# Fan-and-temperature-controller.net
KiCad netlist of a schematic drawn in EAGLE
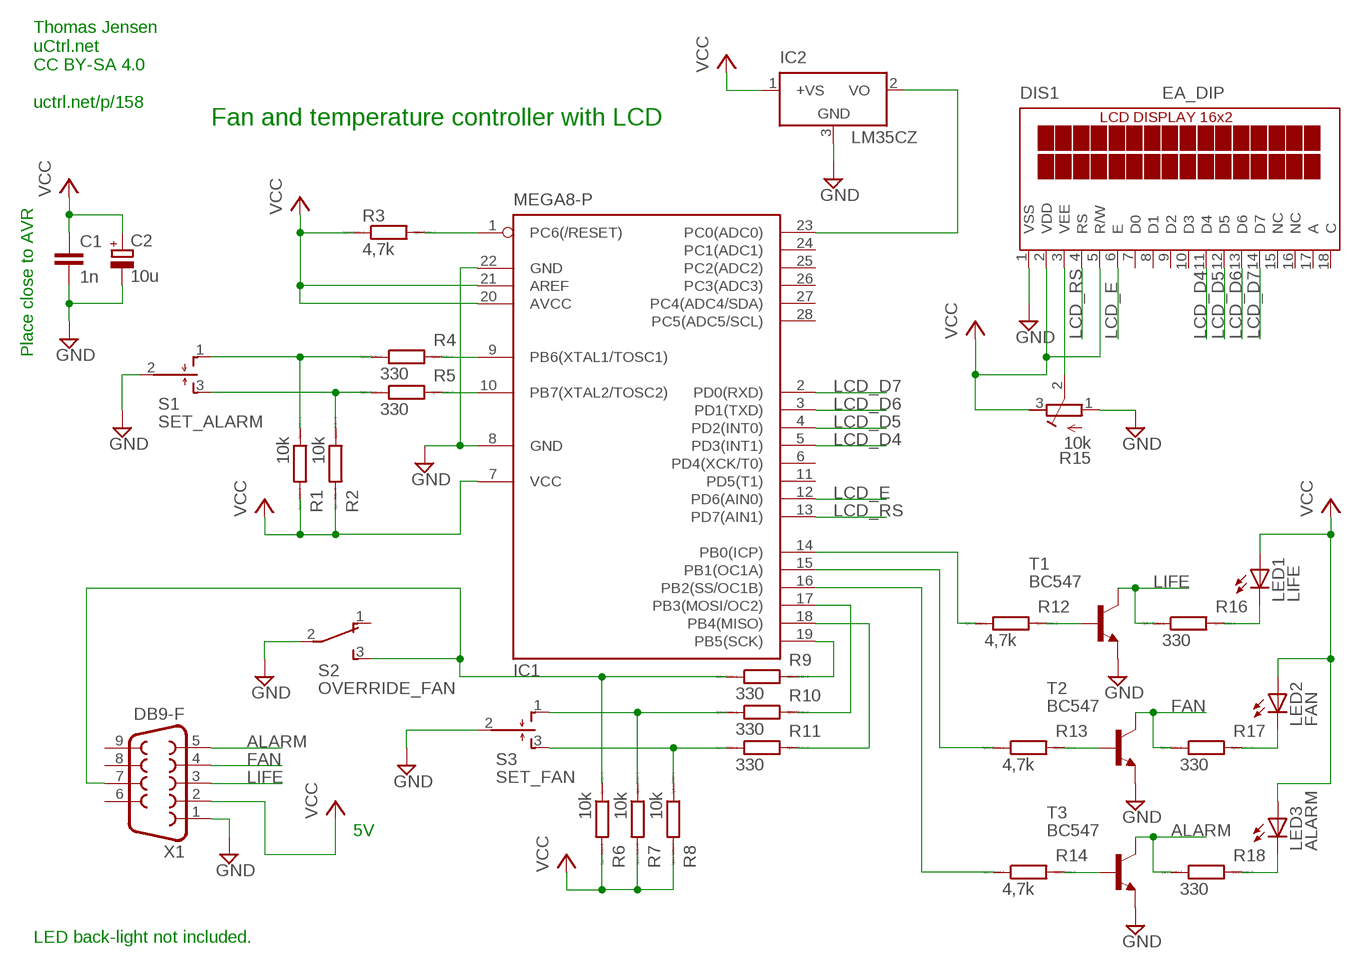
[diagram p0: schematic, sheet 1]

(export (version "E")
  (design (tool "Eeschema 10.0.6"))
  (components
    (comp (ref "C1")
      (value "1n")
      (footprint "eagle-import:C025-024X044")
      (libsource (lib "eagle-import") (part "C-EU025-024X044"))
    )
    (comp (ref "C2")
      (value "10u")
      (footprint "eagle-import:E1,8-4")
      (libsource (lib "eagle-import") (part "CPOL-EUE1.8-4"))
    )
    (comp (ref "DIS1")
      (value "EA_DIP")
      (footprint "eagle-import:EA_DIP")
      (libsource (lib "eagle-import") (part "EA_DIP"))
    )
    (comp (ref "IC1")
      (value "MEGA8-P")
      (footprint "eagle-import:DIL28-3")
      (libsource (lib "eagle-import") (part "MEGA8-P"))
    )
    (comp (ref "IC2")
      (value "LM35CZ")
      (footprint "eagle-import:TO92")
      (libsource (lib "eagle-import") (part "LM35CZ"))
    )
    (comp (ref "LED1")
      (value "LIFE")
      (footprint "eagle-import:LED5MM")
      (libsource (lib "eagle-import") (part "LED5MM"))
    )
    (comp (ref "LED2")
      (value "FAN")
      (footprint "eagle-import:LED5MM")
      (libsource (lib "eagle-import") (part "LED5MM"))
    )
    (comp (ref "LED3")
      (value "ALARM")
      (footprint "eagle-import:LED5MM")
      (libsource (lib "eagle-import") (part "LED5MM"))
    )
    (comp (ref "R1")
      (value "10k")
      (footprint "eagle-import:0204_7")
      (libsource (lib "eagle-import") (part "R0204/7"))
    )
    (comp (ref "R2")
      (value "10k")
      (footprint "eagle-import:0204_7")
      (libsource (lib "eagle-import") (part "R0204/7"))
    )
    (comp (ref "R3")
      (value "4,7k")
      (footprint "eagle-import:0204_7")
      (libsource (lib "eagle-import") (part "R0204/7"))
    )
    (comp (ref "R4")
      (value "330")
      (footprint "eagle-import:0204_7")
      (libsource (lib "eagle-import") (part "R0204/7"))
    )
    (comp (ref "R5")
      (value "330")
      (footprint "eagle-import:0204_7")
      (libsource (lib "eagle-import") (part "R0204/7"))
    )
    (comp (ref "R6")
      (value "10k")
      (footprint "eagle-import:0204_7")
      (libsource (lib "eagle-import") (part "R0204/7"))
    )
    (comp (ref "R7")
      (value "10k")
      (footprint "eagle-import:0204_7")
      (libsource (lib "eagle-import") (part "R0204/7"))
    )
    (comp (ref "R8")
      (value "10k")
      (footprint "eagle-import:0204_7")
      (libsource (lib "eagle-import") (part "R0204/7"))
    )
    (comp (ref "R9")
      (value "330")
      (footprint "eagle-import:0204_7")
      (libsource (lib "eagle-import") (part "R0204/7"))
    )
    (comp (ref "R10")
      (value "330")
      (footprint "eagle-import:0204_7")
      (libsource (lib "eagle-import") (part "R0204/7"))
    )
    (comp (ref "R11")
      (value "330")
      (footprint "eagle-import:0204_7")
      (libsource (lib "eagle-import") (part "R0204/7"))
    )
    (comp (ref "R12")
      (value "4,7k")
      (footprint "eagle-import:0204_7")
      (libsource (lib "eagle-import") (part "R0204/7"))
    )
    (comp (ref "R13")
      (value "4,7k")
      (footprint "eagle-import:0204_7")
      (libsource (lib "eagle-import") (part "R0204/7"))
    )
    (comp (ref "R14")
      (value "4,7k")
      (footprint "eagle-import:0204_7")
      (libsource (lib "eagle-import") (part "R0204/7"))
    )
    (comp (ref "R15")
      (value "10k")
      (footprint "eagle-import:RTRIM3339P")
      (libsource (lib "eagle-import") (part "R-TRIMM3339P"))
    )
    (comp (ref "R16")
      (value "330")
      (footprint "eagle-import:0204_7")
      (libsource (lib "eagle-import") (part "R0204/7"))
    )
    (comp (ref "R17")
      (value "330")
      (footprint "eagle-import:0204_7")
      (libsource (lib "eagle-import") (part "R0204/7"))
    )
    (comp (ref "R18")
      (value "330")
      (footprint "eagle-import:0204_7")
      (libsource (lib "eagle-import") (part "R0204/7"))
    )
    (comp (ref "S1")
      (value "SET_ALARM")
      (footprint "eagle-import:TL3XPO")
      (libsource (lib "eagle-import") (part "TL37PO"))
    )
    (comp (ref "S2")
      (value "OVERRIDE_FAN")
      (footprint "eagle-import:TL3XPO")
      (libsource (lib "eagle-import") (part "TL36PO"))
    )
    (comp (ref "S3")
      (value "SET_FAN")
      (footprint "eagle-import:TL3XPO")
      (libsource (lib "eagle-import") (part "TL37PO"))
    )
    (comp (ref "T1")
      (value "BC547")
      (footprint "eagle-import:TO92")
      (libsource (lib "eagle-import") (part "BC547"))
    )
    (comp (ref "T2")
      (value "BC547")
      (footprint "eagle-import:TO92")
      (libsource (lib "eagle-import") (part "BC547"))
    )
    (comp (ref "T3")
      (value "BC547")
      (footprint "eagle-import:TO92")
      (libsource (lib "eagle-import") (part "BC547"))
    )
    (comp (ref "X1")
      (value "DB9-F")
      (footprint "eagle-import:F09D")
      (libsource (lib "eagle-import") (part "F09D"))
    )
  )
  (nets
    (net (code "1") (name "/ALARM") (class "Default")
      (node (ref "R18") (pin "1") (pinfunction "1_1") (pintype "passive"))
      (node (ref "T3") (pin "3") (pinfunction "C_3") (pintype "passive"))
      (node (ref "X1") (pin "5") (pinfunction "5_5") (pintype "passive"))
    )
    (net (code "2") (name "/FAN") (class "Default")
      (node (ref "R17") (pin "1") (pinfunction "1_1") (pintype "passive"))
      (node (ref "T2") (pin "3") (pinfunction "C_3") (pintype "passive"))
      (node (ref "X1") (pin "4") (pinfunction "4_4") (pintype "passive"))
    )
    (net (code "3") (name "/LCD_D4") (class "Default")
      (node (ref "DIS1") (pin "11") (pinfunction "D4_11") (pintype "input"))
      (node (ref "IC1") (pin "5") (pinfunction "PD3(INT1)_5") (pintype "bidirectional"))
    )
    (net (code "4") (name "/LCD_D5") (class "Default")
      (node (ref "DIS1") (pin "12") (pinfunction "D5_12") (pintype "input"))
      (node (ref "IC1") (pin "4") (pinfunction "PD2(INT0)_4") (pintype "bidirectional"))
    )
    (net (code "5") (name "/LCD_D6") (class "Default")
      (node (ref "DIS1") (pin "13") (pinfunction "D6_13") (pintype "input"))
      (node (ref "IC1") (pin "3") (pinfunction "PD1(TXD)_3") (pintype "bidirectional"))
    )
    (net (code "6") (name "/LCD_D7") (class "Default")
      (node (ref "DIS1") (pin "14") (pinfunction "D7_14") (pintype "input"))
      (node (ref "IC1") (pin "2") (pinfunction "PD0(RXD)_2") (pintype "bidirectional"))
    )
    (net (code "7") (name "/LCD_E") (class "Default")
      (node (ref "DIS1") (pin "6") (pinfunction "E_6") (pintype "input"))
      (node (ref "IC1") (pin "12") (pinfunction "PD6(AIN0)_12") (pintype "bidirectional"))
    )
    (net (code "8") (name "/LCD_RS") (class "Default")
      (node (ref "DIS1") (pin "4") (pinfunction "RS_4") (pintype "input"))
      (node (ref "IC1") (pin "13") (pinfunction "PD7(AIN1)_13") (pintype "bidirectional"))
    )
    (net (code "9") (name "/LIFE") (class "Default")
      (node (ref "R16") (pin "1") (pinfunction "1_1") (pintype "passive"))
      (node (ref "T1") (pin "3") (pinfunction "C_3") (pintype "passive"))
      (node (ref "X1") (pin "3") (pinfunction "3_3") (pintype "passive"))
    )
    (net (code "10") (name "GND") (class "Default")
      (node (ref "C1") (pin "2") (pinfunction "2_2") (pintype "passive"))
      (node (ref "C2") (pin "-") (pinfunction "-_-") (pintype "passive"))
      (node (ref "DIS1") (pin "1") (pinfunction "VSS_1") (pintype "power_in"))
      (node (ref "IC1") (pin "22") (pinfunction "GND_22") (pintype "power_in"))
      (node (ref "IC1") (pin "8") (pinfunction "GND_8") (pintype "power_in"))
      (node (ref "IC2") (pin "3") (pinfunction "GND_3") (pintype "power_in"))
      (node (ref "R15") (pin "1") (pinfunction "A_1") (pintype "passive"))
      (node (ref "S1") (pin "2") (pinfunction "P_2") (pintype "passive"))
      (node (ref "S2") (pin "2") (pinfunction "P_2") (pintype "passive"))
      (node (ref "S3") (pin "2") (pinfunction "P_2") (pintype "passive"))
      (node (ref "T1") (pin "1") (pinfunction "E_1") (pintype "passive"))
      (node (ref "T2") (pin "1") (pinfunction "E_1") (pintype "passive"))
      (node (ref "T3") (pin "1") (pinfunction "E_1") (pintype "passive"))
      (node (ref "X1") (pin "1") (pinfunction "1_1") (pintype "passive"))
    )
    (net (code "11") (name "Net-(DIS1-VEE)") (class "Default")
      (node (ref "DIS1") (pin "3") (pinfunction "VEE_3") (pintype "power_in"))
      (node (ref "R15") (pin "2") (pinfunction "S_2") (pintype "passive"))
    )
    (net (code "12") (name "Net-(IC1-PB0(ICP))") (class "Default")
      (node (ref "IC1") (pin "14") (pinfunction "PB0(ICP)_14") (pintype "bidirectional"))
      (node (ref "R12") (pin "1") (pinfunction "1_1") (pintype "passive"))
    )
    (net (code "13") (name "Net-(IC1-PB1(OC1A))") (class "Default")
      (node (ref "IC1") (pin "15") (pinfunction "PB1(OC1A)_15") (pintype "bidirectional"))
      (node (ref "R13") (pin "1") (pinfunction "1_1") (pintype "passive"))
    )
    (net (code "14") (name "Net-(IC1-PB2(SS{slash}OC1B))") (class "Default")
      (node (ref "IC1") (pin "16") (pinfunction "PB2(SS/OC1B)_16") (pintype "bidirectional"))
      (node (ref "R14") (pin "1") (pinfunction "1_1") (pintype "passive"))
    )
    (net (code "15") (name "Net-(IC1-PB3(MOSI{slash}OC2))") (class "Default")
      (node (ref "IC1") (pin "17") (pinfunction "PB3(MOSI/OC2)_17") (pintype "bidirectional"))
      (node (ref "R10") (pin "2") (pinfunction "2_2") (pintype "passive"))
    )
    (net (code "16") (name "Net-(IC1-PB4(MISO))") (class "Default")
      (node (ref "IC1") (pin "18") (pinfunction "PB4(MISO)_18") (pintype "bidirectional"))
      (node (ref "R11") (pin "2") (pinfunction "2_2") (pintype "passive"))
    )
    (net (code "17") (name "Net-(IC1-PB5(SCK))") (class "Default")
      (node (ref "IC1") (pin "19") (pinfunction "PB5(SCK)_19") (pintype "bidirectional"))
      (node (ref "R9") (pin "2") (pinfunction "2_2") (pintype "passive"))
    )
    (net (code "18") (name "Net-(IC1-PB6(XTAL1{slash}TOSC1))") (class "Default")
      (node (ref "IC1") (pin "9") (pinfunction "PB6(XTAL1/TOSC1)_9") (pintype "bidirectional"))
      (node (ref "R4") (pin "2") (pinfunction "2_2") (pintype "passive"))
    )
    (net (code "19") (name "Net-(IC1-PB7(XTAL2{slash}TOSC2))") (class "Default")
      (node (ref "IC1") (pin "10") (pinfunction "PB7(XTAL2/TOSC2)_10") (pintype "bidirectional"))
      (node (ref "R5") (pin "2") (pinfunction "2_2") (pintype "passive"))
    )
    (net (code "20") (name "Net-(IC1-PC0(ADC0))") (class "Default")
      (node (ref "IC1") (pin "23") (pinfunction "PC0(ADC0)_23") (pintype "bidirectional"))
      (node (ref "IC2") (pin "2") (pinfunction "VO_2") (pintype "input"))
    )
    (net (code "21") (name "Net-(IC1-PC6({slash}RESET))") (class "Default")
      (node (ref "IC1") (pin "1") (pinfunction "PC6(/RESET)_1") (pintype "bidirectional"))
      (node (ref "R3") (pin "2") (pinfunction "2_2") (pintype "passive"))
    )
    (net (code "22") (name "Net-(LED1-C)") (class "Default")
      (node (ref "LED1") (pin "K") (pinfunction "C_K") (pintype "passive"))
      (node (ref "R16") (pin "2") (pinfunction "2_2") (pintype "passive"))
    )
    (net (code "23") (name "Net-(LED2-C)") (class "Default")
      (node (ref "LED2") (pin "K") (pinfunction "C_K") (pintype "passive"))
      (node (ref "R17") (pin "2") (pinfunction "2_2") (pintype "passive"))
    )
    (net (code "24") (name "Net-(LED3-C)") (class "Default")
      (node (ref "LED3") (pin "K") (pinfunction "C_K") (pintype "passive"))
      (node (ref "R18") (pin "2") (pinfunction "2_2") (pintype "passive"))
    )
    (net (code "25") (name "Net-(S1-O)") (class "Default")
      (node (ref "R1") (pin "1") (pinfunction "1_1") (pintype "passive"))
      (node (ref "R4") (pin "1") (pinfunction "1_1") (pintype "passive"))
      (node (ref "S1") (pin "1") (pinfunction "O_1") (pintype "passive"))
    )
    (net (code "26") (name "Net-(S1-S)") (class "Default")
      (node (ref "R2") (pin "1") (pinfunction "1_1") (pintype "passive"))
      (node (ref "R5") (pin "1") (pinfunction "1_1") (pintype "passive"))
      (node (ref "S1") (pin "3") (pinfunction "S_3") (pintype "passive"))
    )
    (net (code "27") (name "Net-(S2-S)") (class "Default")
      (node (ref "R6") (pin "1") (pinfunction "1_1") (pintype "passive"))
      (node (ref "R9") (pin "1") (pinfunction "1_1") (pintype "passive"))
      (node (ref "S2") (pin "3") (pinfunction "S_3") (pintype "passive"))
      (node (ref "X1") (pin "7") (pinfunction "7_7") (pintype "passive"))
    )
    (net (code "28") (name "Net-(S3-O)") (class "Default")
      (node (ref "R10") (pin "1") (pinfunction "1_1") (pintype "passive"))
      (node (ref "R7") (pin "1") (pinfunction "1_1") (pintype "passive"))
      (node (ref "S3") (pin "1") (pinfunction "O_1") (pintype "passive"))
    )
    (net (code "29") (name "Net-(S3-S)") (class "Default")
      (node (ref "R11") (pin "1") (pinfunction "1_1") (pintype "passive"))
      (node (ref "R8") (pin "1") (pinfunction "1_1") (pintype "passive"))
      (node (ref "S3") (pin "3") (pinfunction "S_3") (pintype "passive"))
    )
    (net (code "30") (name "Net-(T1-B)") (class "Default")
      (node (ref "R12") (pin "2") (pinfunction "2_2") (pintype "passive"))
      (node (ref "T1") (pin "2") (pinfunction "B_2") (pintype "passive"))
    )
    (net (code "31") (name "Net-(T2-B)") (class "Default")
      (node (ref "R13") (pin "2") (pinfunction "2_2") (pintype "passive"))
      (node (ref "T2") (pin "2") (pinfunction "B_2") (pintype "passive"))
    )
    (net (code "32") (name "Net-(T3-B)") (class "Default")
      (node (ref "R14") (pin "2") (pinfunction "2_2") (pintype "passive"))
      (node (ref "T3") (pin "2") (pinfunction "B_2") (pintype "passive"))
    )
    (net (code "33") (name "VCC") (class "Default")
      (node (ref "C1") (pin "1") (pinfunction "1_1") (pintype "passive"))
      (node (ref "C2") (pin "+") (pinfunction "+_+") (pintype "passive"))
      (node (ref "DIS1") (pin "2") (pinfunction "VDD_2") (pintype "power_in"))
      (node (ref "DIS1") (pin "5") (pinfunction "R/W_5") (pintype "input"))
      (node (ref "IC1") (pin "20") (pinfunction "AVCC_20") (pintype "power_in"))
      (node (ref "IC1") (pin "21") (pinfunction "AREF_21") (pintype "passive"))
      (node (ref "IC1") (pin "7") (pinfunction "VCC_7") (pintype "power_in"))
      (node (ref "IC2") (pin "1") (pinfunction "+VS_1") (pintype "input"))
      (node (ref "LED1") (pin "A") (pinfunction "A_A") (pintype "passive"))
      (node (ref "LED2") (pin "A") (pinfunction "A_A") (pintype "passive"))
      (node (ref "LED3") (pin "A") (pinfunction "A_A") (pintype "passive"))
      (node (ref "R1") (pin "2") (pinfunction "2_2") (pintype "passive"))
      (node (ref "R15") (pin "3") (pinfunction "E_3") (pintype "passive"))
      (node (ref "R2") (pin "2") (pinfunction "2_2") (pintype "passive"))
      (node (ref "R3") (pin "1") (pinfunction "1_1") (pintype "passive"))
      (node (ref "R6") (pin "2") (pinfunction "2_2") (pintype "passive"))
      (node (ref "R7") (pin "2") (pinfunction "2_2") (pintype "passive"))
      (node (ref "R8") (pin "2") (pinfunction "2_2") (pintype "passive"))
      (node (ref "X1") (pin "2") (pinfunction "2_2") (pintype "passive"))
    )
    (net (code "34") (name "unconnected-(DIS1-A-Pad17)") (class "Default")
      (node (ref "DIS1") (pin "17") (pinfunction "A_17") (pintype "passive"))
    )
    (net (code "35") (name "unconnected-(DIS1-C-Pad18)") (class "Default")
      (node (ref "DIS1") (pin "18") (pinfunction "C_18") (pintype "passive"))
    )
    (net (code "36") (name "unconnected-(DIS1-D0-Pad7)") (class "Default")
      (node (ref "DIS1") (pin "7") (pinfunction "D0_7") (pintype "input"))
    )
    (net (code "37") (name "unconnected-(DIS1-D1-Pad8)") (class "Default")
      (node (ref "DIS1") (pin "8") (pinfunction "D1_8") (pintype "input"))
    )
    (net (code "38") (name "unconnected-(DIS1-D2-Pad9)") (class "Default")
      (node (ref "DIS1") (pin "9") (pinfunction "D2_9") (pintype "input"))
    )
    (net (code "39") (name "unconnected-(DIS1-D3-Pad10)") (class "Default")
      (node (ref "DIS1") (pin "10") (pinfunction "D3_10") (pintype "input"))
    )
    (net (code "40") (name "unconnected-(DIS1-NC-Pad15)") (class "Default")
      (node (ref "DIS1") (pin "15") (pinfunction "NC_15") (pintype "no_connect"))
    )
    (net (code "41") (name "unconnected-(DIS1-NC-Pad16)") (class "Default")
      (node (ref "DIS1") (pin "16") (pinfunction "NC_16") (pintype "no_connect"))
    )
    (net (code "42") (name "unconnected-(IC1-PC1(ADC1)-Pad24)") (class "Default")
      (node (ref "IC1") (pin "24") (pinfunction "PC1(ADC1)_24") (pintype "bidirectional"))
    )
    (net (code "43") (name "unconnected-(IC1-PC2(ADC2)-Pad25)") (class "Default")
      (node (ref "IC1") (pin "25") (pinfunction "PC2(ADC2)_25") (pintype "bidirectional"))
    )
    (net (code "44") (name "unconnected-(IC1-PC3(ADC3)-Pad26)") (class "Default")
      (node (ref "IC1") (pin "26") (pinfunction "PC3(ADC3)_26") (pintype "bidirectional"))
    )
    (net (code "45") (name "unconnected-(IC1-PC4(ADC4{slash}SDA)-Pad27)") (class "Default")
      (node (ref "IC1") (pin "27") (pinfunction "PC4(ADC4/SDA)_27") (pintype "bidirectional"))
    )
    (net (code "46") (name "unconnected-(IC1-PC5(ADC5{slash}SCL)-Pad28)") (class "Default")
      (node (ref "IC1") (pin "28") (pinfunction "PC5(ADC5/SCL)_28") (pintype "bidirectional"))
    )
    (net (code "47") (name "unconnected-(IC1-PD4(XCK{slash}T0)-Pad6)") (class "Default")
      (node (ref "IC1") (pin "6") (pinfunction "PD4(XCK/T0)_6") (pintype "bidirectional"))
    )
    (net (code "48") (name "unconnected-(IC1-PD5(T1)-Pad11)") (class "Default")
      (node (ref "IC1") (pin "11") (pinfunction "PD5(T1)_11") (pintype "bidirectional"))
    )
    (net (code "49") (name "unconnected-(S2-O-Pad1)") (class "Default")
      (node (ref "S2") (pin "1") (pinfunction "O_1") (pintype "passive"))
    )
    (net (code "50") (name "unconnected-(X1-Pad6)") (class "Default")
      (node (ref "X1") (pin "6") (pinfunction "6_6") (pintype "passive"))
    )
    (net (code "51") (name "unconnected-(X1-Pad8)") (class "Default")
      (node (ref "X1") (pin "8") (pinfunction "8_8") (pintype "passive"))
    )
    (net (code "52") (name "unconnected-(X1-Pad9)") (class "Default")
      (node (ref "X1") (pin "9") (pinfunction "9_9") (pintype "passive"))
    )
  )
)
